# payload.net
KiCad netlist of a schematic drawn in Altium Designer
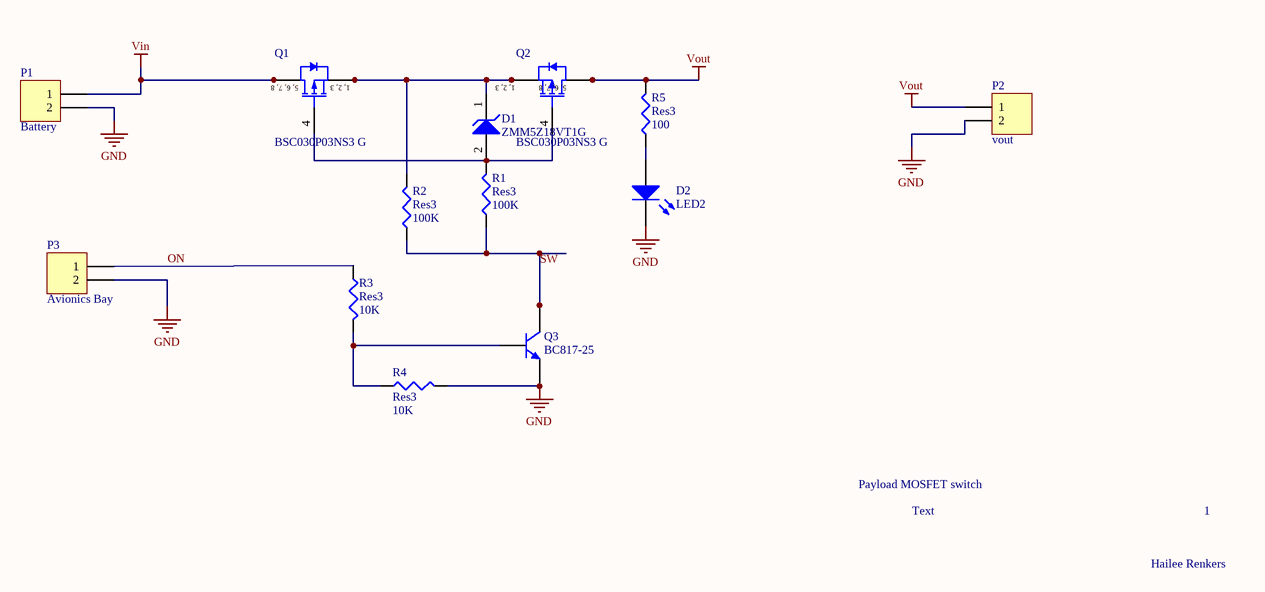
[diagram p0: payload.SchDoc]

(export (version "E")
  (design (tool "Eeschema 10.0.6"))
  (components
    (comp (ref "D1")
      (value "ZMM5Z18VT1G")
      (footprint "ONSC-SOD-523-2-502-01_V")
      (description "Zener Voltage Regulator, 500 mW, 2-Pin SOD-523, Pb-Free, Tape and Reel")
      (fields (field (name "MANUFACTURER") "On Semiconductor"))
      (libsource (lib "ON Semi Zener Diodes") (part "ZMM5Z18VT1G"))
    )
    (comp (ref "D2")
      (value "LED2")
      (footprint "3.2X1.6X1.1")
      (description "Typical RED, GREEN, YELLOW, AMBER GaAs LED")
      (fields (field (name "PUBLISHER") "Altium Limited"))
      (libsource (lib "Miscellaneous Devices") (part "LED2"))
    )
    (comp (ref "P1")
      (value "Battery")
      (footprint "HDR1X2")
      (description "Header, 2-Pin")
      (fields (field (name "PUBLISHER") "Altium Limited"))
      (libsource (lib "") (part "Header 2_1"))
    )
    (comp (ref "P2")
      (value "vout")
      (footprint "HDR1X2")
      (description "Header, 2-Pin")
      (fields (field (name "PUBLISHER") "Altium Limited"))
      (libsource (lib "Miscellaneous Connectors") (part "Header 2"))
    )
    (comp (ref "P3")
      (value "Avionics Bay")
      (footprint "HDR1X2")
      (description "Header, 2-Pin")
      (fields (field (name "PUBLISHER") "Altium Limited"))
      (libsource (lib "") (part "Header 2_1"))
    )
    (comp (ref "Q1")
      (value "BSC030P03NS3 G")
      (footprint "INF-PG-TDSON-8-1_V")
      (fields (field (name "MANUFACTURER") "Infineon"))
      (libsource (lib "Infineon_Power_MOSFET") (part "BSC030P03NS3 G"))
    )
    (comp (ref "Q2")
      (value "BSC030P03NS3 G")
      (footprint "INF-PG-TDSON-8-1_V")
      (fields (field (name "MANUFACTURER") "Infineon"))
      (libsource (lib "Infineon_Power_MOSFET") (part "BSC030P03NS3 G"))
    )
    (comp (ref "Q3")
      (value "BC817-25")
      (footprint "SOT-23A_N")
      (description "NPN General Purpose Amplifier")
      (fields (field (name "PUBLISHER") "Altium Limited"))
      (libsource (lib "FSC Discrete BJT") (part "BC817-25"))
    )
    (comp (ref "R1")
      (value "Res3")
      (footprint "J1-0603")
      (description "Resistor")
      (fields (field (name "ALTIUM_VALUE") "100K") (field (name "PUBLISHER") "Altium Limited"))
      (libsource (lib "Miscellaneous Devices") (part "Res3"))
    )
    (comp (ref "R2")
      (value "Res3")
      (footprint "J1-0603")
      (description "Resistor")
      (fields (field (name "ALTIUM_VALUE") "100K") (field (name "PUBLISHER") "Altium Limited"))
      (libsource (lib "Miscellaneous Devices") (part "Res3"))
    )
    (comp (ref "R3")
      (value "Res3")
      (footprint "J1-0603")
      (description "Resistor")
      (fields (field (name "ALTIUM_VALUE") "10K") (field (name "PUBLISHER") "Altium Limited"))
      (libsource (lib "Miscellaneous Devices") (part "Res3"))
    )
    (comp (ref "R4")
      (value "Res3")
      (footprint "J1-0603")
      (description "Resistor")
      (fields (field (name "ALTIUM_VALUE") "10K") (field (name "PUBLISHER") "Altium Limited"))
      (libsource (lib "Miscellaneous Devices") (part "Res3"))
    )
    (comp (ref "R5")
      (value "Res3")
      (footprint "J1-0603")
      (description "Resistor")
      (fields (field (name "ALTIUM_VALUE") "100") (field (name "PUBLISHER") "Altium Limited"))
      (libsource (lib "Miscellaneous Devices") (part "Res3"))
    )
  )
  (nets
    (net (code "2") (name "/ON") (class "Default")
      (node (ref "P3") (pin "1") (pinfunction "1_1") (pintype "passive"))
      (node (ref "R3") (pin "1") (pinfunction "1_1") (pintype "passive"))
    )
    (net (code "3") (name "/SW") (class "Default")
      (node (ref "Q3") (pin "3") (pinfunction "C_3") (pintype "passive"))
      (node (ref "R1") (pin "1") (pinfunction "1_1") (pintype "passive"))
      (node (ref "R2") (pin "1") (pinfunction "1_1") (pintype "passive"))
    )
    (net (code "4") (name "GND") (class "Default")
      (node (ref "D2") (pin "2") (pinfunction "K_2") (pintype "passive"))
      (node (ref "P1") (pin "2") (pinfunction "2_2") (pintype "passive"))
      (node (ref "P2") (pin "2") (pinfunction "2_2") (pintype "passive"))
      (node (ref "P3") (pin "2") (pinfunction "2_2") (pintype "passive"))
      (node (ref "Q3") (pin "2") (pinfunction "E_2") (pintype "passive"))
      (node (ref "R4") (pin "2") (pinfunction "2_2") (pintype "passive"))
    )
    (net (code "5") (name "Net-(D1-A)") (class "Default")
      (node (ref "D1") (pin "2") (pinfunction "A_2") (pintype "passive"))
      (node (ref "Q1") (pin "4") (pinfunction "GATE_4") (pintype "passive"))
      (node (ref "Q2") (pin "4") (pinfunction "GATE_4") (pintype "passive"))
      (node (ref "R1") (pin "2") (pinfunction "2_2") (pintype "passive"))
    )
    (net (code "6") (name "Net-(D1-K)") (class "Default")
      (node (ref "D1") (pin "1") (pinfunction "K_1") (pintype "passive"))
      (node (ref "Q1") (pin "1") (pinfunction "SOURCE_1") (pintype "passive"))
      (node (ref "Q1") (pin "2") (pinfunction "SOURCE_2") (pintype "passive"))
      (node (ref "Q1") (pin "3") (pinfunction "SOURCE_3") (pintype "passive"))
      (node (ref "Q2") (pin "1") (pinfunction "SOURCE_1") (pintype "passive"))
      (node (ref "Q2") (pin "2") (pinfunction "SOURCE_2") (pintype "passive"))
      (node (ref "Q2") (pin "3") (pinfunction "SOURCE_3") (pintype "passive"))
      (node (ref "R2") (pin "2") (pinfunction "2_2") (pintype "passive"))
    )
    (net (code "7") (name "Net-(D2-A)") (class "Default")
      (node (ref "D2") (pin "1") (pinfunction "A_1") (pintype "passive"))
      (node (ref "R5") (pin "1") (pinfunction "1_1") (pintype "passive"))
    )
    (net (code "8") (name "Net-(Q3-B)") (class "Default")
      (node (ref "Q3") (pin "1") (pinfunction "B_1") (pintype "passive"))
      (node (ref "R3") (pin "2") (pinfunction "2_2") (pintype "passive"))
      (node (ref "R4") (pin "1") (pinfunction "1_1") (pintype "passive"))
    )
    (net (code "9") (name "Vin") (class "Default")
      (node (ref "P1") (pin "1") (pinfunction "1_1") (pintype "passive"))
      (node (ref "Q1") (pin "5") (pinfunction "DRAIN_5") (pintype "passive"))
      (node (ref "Q1") (pin "6") (pinfunction "DRAIN_6") (pintype "passive"))
      (node (ref "Q1") (pin "7") (pinfunction "DRAIN_7") (pintype "passive"))
      (node (ref "Q1") (pin "8") (pinfunction "DRAIN_8") (pintype "passive"))
    )
    (net (code "10") (name "Vout") (class "Default")
      (node (ref "P2") (pin "1") (pinfunction "1_1") (pintype "passive"))
      (node (ref "Q2") (pin "5") (pinfunction "DRAIN_5") (pintype "passive"))
      (node (ref "Q2") (pin "6") (pinfunction "DRAIN_6") (pintype "passive"))
      (node (ref "Q2") (pin "7") (pinfunction "DRAIN_7") (pintype "passive"))
      (node (ref "Q2") (pin "8") (pinfunction "DRAIN_8") (pintype "passive"))
      (node (ref "R5") (pin "2") (pinfunction "2_2") (pintype "passive"))
    )
  )
)
